# Header_-_Digital_Pot_4131.net
KiCad netlist of a schematic drawn in EAGLE
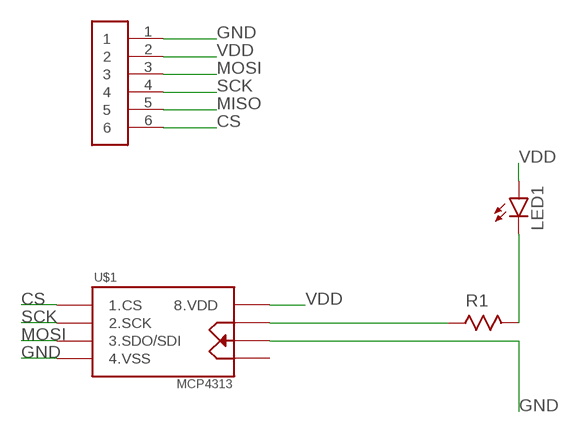
[diagram p0: schematic, sheet 1]

(export (version "E")
  (design (tool "Eeschema 10.0.6"))
  (components
    (comp (ref "LED1")
      (value "LED5MM")
      (footprint "eagle-import:LED5MM")
      (libsource (lib "eagle-import") (part "LED5MM"))
    )
    (comp (ref "R1")
      (value "R204-5")
      (footprint "eagle-import:0204_5")
      (libsource (lib "eagle-import") (part "R204-5"))
    )
    (comp (ref "U$1")
      (value "MCP4131")
      (footprint "eagle-import:DIL08")
      (libsource (lib "eagle-import") (part "MCP4131"))
    )
    (comp (ref "U$2")
      (value "PINS_6SQUARE")
      (footprint "eagle-import:PINS_6")
      (libsource (lib "eagle-import") (part "PINS_6SQUARE"))
    )
  )
  (nets
    (net (code "1") (name "/CS") (class "Default")
      (node (ref "U$1") (pin "1") (pinfunction "1.CS_1") (pintype "bidirectional"))
      (node (ref "U$2") (pin "6") (pinfunction "6_6") (pintype "bidirectional"))
    )
    (net (code "2") (name "/GND") (class "Default")
      (node (ref "U$1") (pin "4") (pinfunction "4.VSS_4") (pintype "bidirectional"))
      (node (ref "U$1") (pin "6") (pinfunction "6.P0W_6") (pintype "bidirectional"))
      (node (ref "U$2") (pin "1") (pinfunction "1_1") (pintype "bidirectional"))
    )
    (net (code "3") (name "/MISO") (class "Default")
      (node (ref "U$2") (pin "5") (pinfunction "5_5") (pintype "bidirectional"))
    )
    (net (code "4") (name "/MOSI") (class "Default")
      (node (ref "U$1") (pin "3") (pinfunction "3.SDO/SDI_3") (pintype "bidirectional"))
      (node (ref "U$2") (pin "3") (pinfunction "3_3") (pintype "bidirectional"))
    )
    (net (code "5") (name "/SCK") (class "Default")
      (node (ref "U$1") (pin "2") (pinfunction "2.SCK_2") (pintype "bidirectional"))
      (node (ref "U$2") (pin "4") (pinfunction "4_4") (pintype "bidirectional"))
    )
    (net (code "6") (name "/VDD") (class "Default")
      (node (ref "LED1") (pin "A") (pinfunction "A_A") (pintype "passive"))
      (node (ref "U$1") (pin "8") (pinfunction "8.VDD_8") (pintype "bidirectional"))
      (node (ref "U$2") (pin "2") (pinfunction "2_2") (pintype "bidirectional"))
    )
    (net (code "7") (name "Net-(LED1-C)") (class "Default")
      (node (ref "LED1") (pin "K") (pinfunction "C_K") (pintype "passive"))
      (node (ref "R1") (pin "2") (pinfunction "P$2_2") (pintype "bidirectional"))
    )
    (net (code "8") (name "Net-(R1-P$1)") (class "Default")
      (node (ref "R1") (pin "1") (pinfunction "P$1_1") (pintype "bidirectional"))
      (node (ref "U$1") (pin "7") (pinfunction "7.P0B_7") (pintype "bidirectional"))
    )
    (net (code "9") (name "unconnected-(U$1-5.P0A-Pad5)") (class "Default")
      (node (ref "U$1") (pin "5") (pinfunction "5.P0A_5") (pintype "bidirectional"))
    )
  )
)
